# 03-POWER.net
KiCad netlist of a schematic drawn in Altium Designer
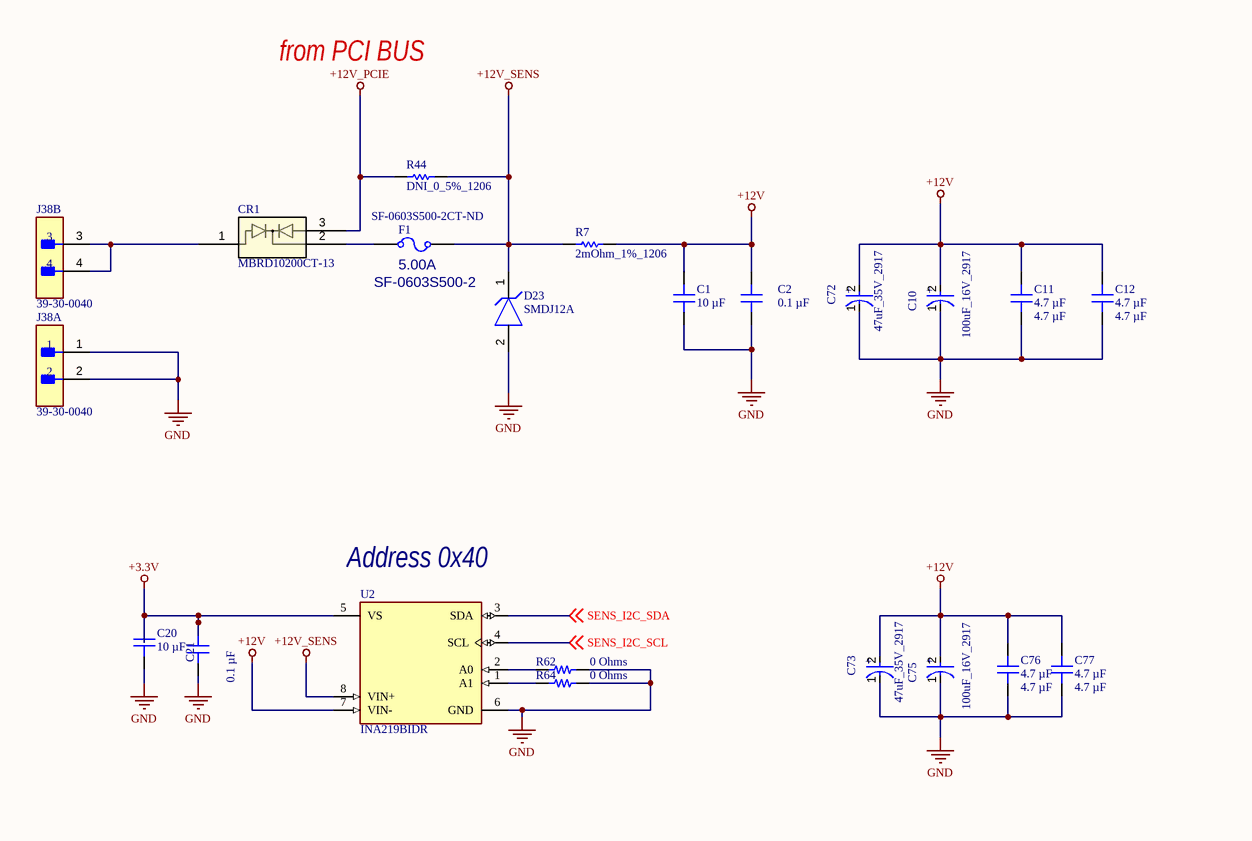
[diagram p0: 03-POWER.SchDoc, left]
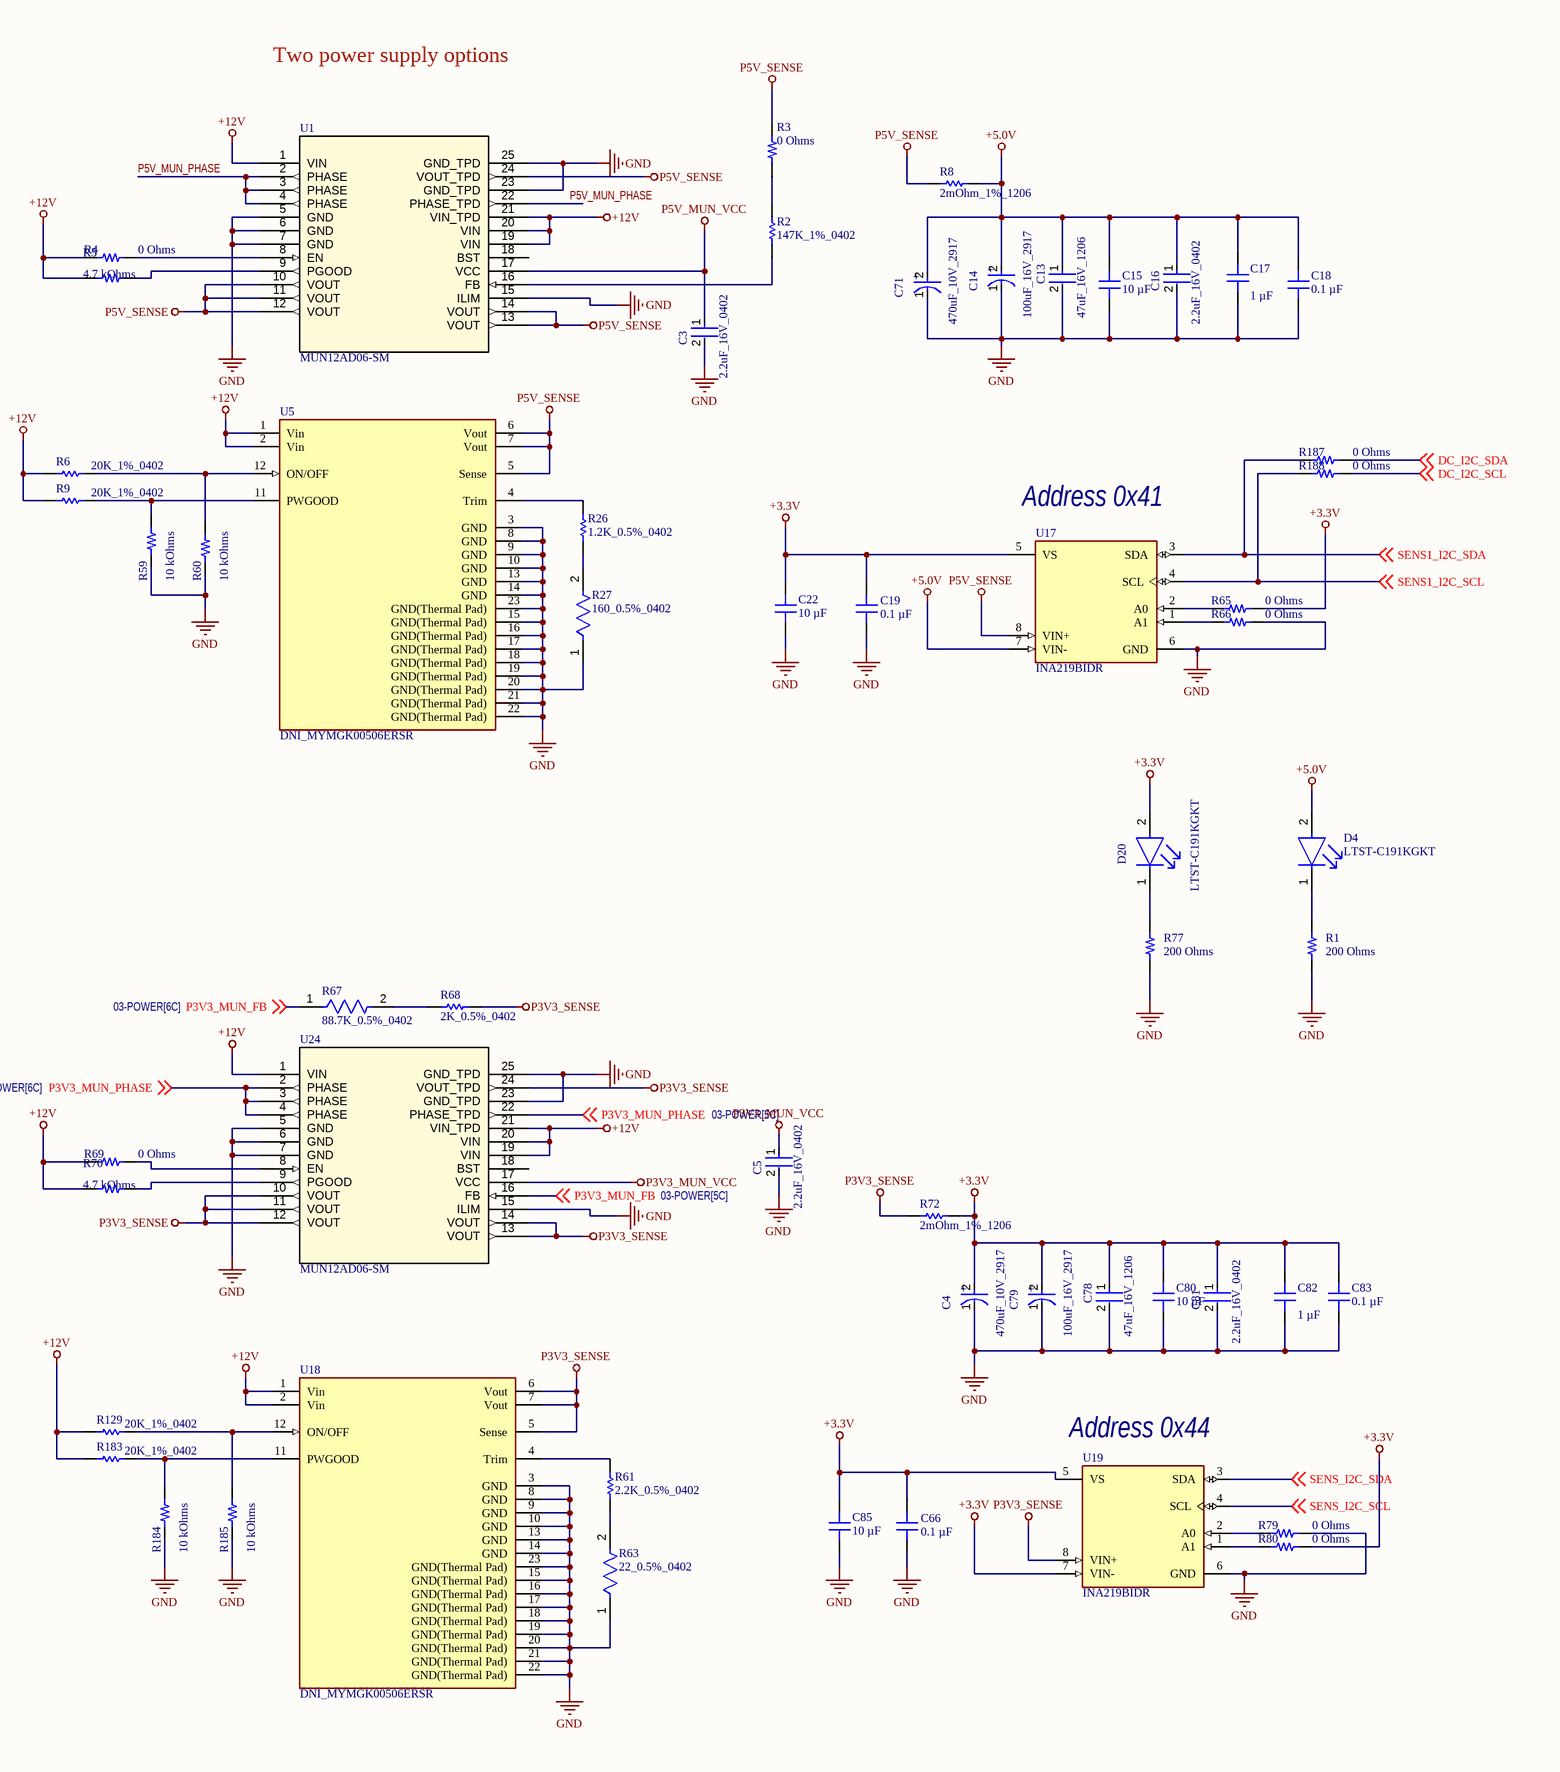
[diagram p1: 03-POWER.SchDoc, right]

(export (version "E")
  (design (tool "Eeschema 10.0.6"))
  (components
    (comp (ref "C1")
      (value "10 µF")
      (footprint "MURATA GRM21B 0805_2012")
      (description "CAP CER 10UF 25V X5R 0805")
      (fields
        (field (name "PART NUMBER") "GRM21BR61E106KA73L")
        (field (name "MANUFACTURER") "Murata Electronics")
      )
      (libsource (lib "Celestial Altium Library - altium_library") (part "Capacitor"))
    )
    (comp (ref "C2")
      (value "0.1 µF")
      (footprint "CAP 0402_1005")
      (description "CAP CER 0.1UF 50V X7R 0402")
      (fields (field (name "MANUFACTURER") "Yageo") (field (name "PART NUMBER") "CC0402KRX7R9BB104"))
      (libsource (lib "Celestial Altium Library - altium_library") (part "Capacitor"))
    )
    (comp (ref "C3")
      (value "2.2uF_16V_0402")
      (footprint "FP-C1005-050-0_05-IPC_A")
      (description "Multilayer Ceramic Capacitors 2.2μF ±10% 16V X5R SMD 0402")
      (fields (field (name "TOLERANCE") "10%"))
      (libsource (lib "Altium Content Vault") (part "b4654b650e69147ec39a6b967a45e02"))
    )
    (comp (ref "C4")
      (value "470uF_10V_2917")
      (footprint "FP-TAJE-MFG")
      (description "470uF 10V  ±10% 500mΩ 2917  SMD Tantalum Capacitor")
      (fields (field (name "TOLERANCE") "10%") (field (name "VOLTAGE") "10V"))
      (libsource (lib "Altium Content Vault") (part "203bc49f2ac43e59fd269a8c329ed05"))
    )
    (comp (ref "C5")
      (value "2.2uF_16V_0402")
      (footprint "FP-C1005-050-0_05-IPC_A")
      (description "Multilayer Ceramic Capacitors 2.2μF ±10% 16V X5R SMD 0402")
      (fields (field (name "TOLERANCE") "10%"))
      (libsource (lib "Altium Content Vault") (part "b4654b650e69147ec39a6b967a45e02"))
    )
    (comp (ref "C10")
      (value "100uF_16V_2917")
      (footprint "FP-T495D107K016ATE125-MFG")
      (description "CAP TANT 100UF 10% 16V 2917")
      (fields (field (name "VOLTAGE") "16V") (field (name "TOLERANCE") "10%"))
      (libsource (lib "Altium Content Vault") (part "a00bbbee19879c290e62620ae7e47b1"))
    )
    (comp (ref "C11")
      (value "4.7 µF")
      (footprint "MURATA CAP GRM31C 1206_3216")
      (description "CAP CER 4.7UF 50V X7R 1206")
      (fields
        (field (name "TOLERANCE") "±10%")
        (field (name "PART NUMBER") "GRM31CR71H475KA12L")
        (field (name "ALTIUM_VALUE") "4.7 µF")
      )
      (libsource (lib "Celestial Altium Library - altium_library") (part "Capacitor"))
    )
    (comp (ref "C12")
      (value "4.7 µF")
      (footprint "MURATA CAP GRM31C 1206_3216")
      (description "CAP CER 4.7UF 50V X7R 1206")
      (fields
        (field (name "TOLERANCE") "±10%")
        (field (name "PART NUMBER") "GRM31CR71H475KA12L")
        (field (name "ALTIUM_VALUE") "4.7 µF")
      )
      (libsource (lib "Celestial Altium Library - altium_library") (part "Capacitor"))
    )
    (comp (ref "C13")
      (value "47uF_16V_1206")
      (footprint "FP-C3216-160-0_2-MFG")
      (description "Multilayer Ceramic Capacitors 47uF ±20% 16V X5R SMD 1206")
      (fields (field (name "TOLERANCE") "20%"))
      (libsource (lib "Altium Content Vault") (part "11868f565c42a9108669ba33697ecf6"))
    )
    (comp (ref "C14")
      (value "100uF_16V_2917")
      (footprint "FP-T495D107K016ATE125-MFG")
      (description "CAP TANT 100UF 10% 16V 2917")
      (fields (field (name "VOLTAGE") "16V") (field (name "TOLERANCE") "10%"))
      (libsource (lib "Altium Content Vault") (part "a00bbbee19879c290e62620ae7e47b1"))
    )
    (comp (ref "C15")
      (value "10 µF")
      (footprint "MURATA GRM21B 0805_2012")
      (description "CAP CER 10UF 25V X5R 0805")
      (fields (field (name "TOLERANCE") "±10%") (field (name "PART NUMBER") "GRM21BR61E106KA73L"))
      (libsource (lib "Celestial Altium Library - altium_library") (part "Capacitor"))
    )
    (comp (ref "C16")
      (value "2.2uF_16V_0402")
      (footprint "FP-C1005-050-0_05-IPC_A")
      (description "Multilayer Ceramic Capacitors 2.2μF ±10% 16V X5R SMD 0402")
      (fields (field (name "TOLERANCE") "10%"))
      (libsource (lib "Altium Content Vault") (part "b4654b650e69147ec39a6b967a45e02"))
    )
    (comp (ref "C17")
      (value "1 µF")
      (footprint "CAP 0402_1005")
      (description "CAP CER 1UF 25V X5R 0402")
      (fields (field (name "TOLERANCE") "±10%") (field (name "PART NUMBER") "CC0402KRX5R8BB105"))
      (libsource (lib "Celestial Altium Library - altium_library") (part "Capacitor"))
    )
    (comp (ref "C18")
      (value "0.1 µF")
      (footprint "CAP 0402_1005")
      (description "CAP CER 0.1UF 50V X7R 0402")
      (fields (field (name "TOLERANCE") "±10%") (field (name "PART NUMBER") "CC0402KRX7R9BB104"))
      (libsource (lib "Celestial Altium Library - altium_library") (part "Capacitor"))
    )
    (comp (ref "C19")
      (value "0.1 µF")
      (footprint "CAP 0402_1005")
      (description "CAP CER 0.1UF 50V X7R 0402")
      (fields (field (name "PART NUMBER") "CC0402KRX7R9BB104") (field (name "MANUFACTURER") "Yageo"))
      (libsource (lib "Celestial Altium Library - altium_library") (part "Capacitor"))
    )
    (comp (ref "C20")
      (value "10 µF")
      (footprint "MURATA GRM21B 0805_2012")
      (description "CAP CER 10UF 25V X5R 0805")
      (fields (field (name "TOLERANCE") "±10%") (field (name "PART NUMBER") "GRM21BR61E106KA73L"))
      (libsource (lib "Celestial Altium Library - altium_library") (part "Capacitor"))
    )
    (comp (ref "C21")
      (value "0.1 µF")
      (footprint "CAP 0402_1005")
      (description "CAP CER 0.1UF 50V X7R 0402")
      (fields (field (name "PART NUMBER") "CC0402KRX7R9BB104") (field (name "MANUFACTURER") "Yageo"))
      (libsource (lib "Celestial Altium Library - altium_library") (part "Capacitor"))
    )
    (comp (ref "C22")
      (value "10 µF")
      (footprint "MURATA GRM21B 0805_2012")
      (description "CAP CER 10UF 25V X5R 0805")
      (fields (field (name "TOLERANCE") "±10%") (field (name "PART NUMBER") "GRM21BR61E106KA73L"))
      (libsource (lib "Celestial Altium Library - altium_library") (part "Capacitor"))
    )
    (comp (ref "C66")
      (value "0.1 µF")
      (footprint "CAP 0402_1005")
      (description "CAP CER 0.1UF 50V X7R 0402")
      (fields (field (name "PART NUMBER") "CC0402KRX7R9BB104") (field (name "MANUFACTURER") "Yageo"))
      (libsource (lib "Celestial Altium Library - altium_library") (part "Capacitor"))
    )
    (comp (ref "C71")
      (value "470uF_10V_2917")
      (footprint "FP-TAJE-MFG")
      (description "470uF 10V  ±10% 500mΩ 2917  SMD Tantalum Capacitor")
      (fields (field (name "TOLERANCE") "10%") (field (name "VOLTAGE") "10V"))
      (libsource (lib "Altium Content Vault") (part "203bc49f2ac43e59fd269a8c329ed05"))
    )
    (comp (ref "C72")
      (value "47uF_35V_2917")
      (footprint "FP-T521X476M035ATE030-MFG")
      (description "CAP TANT POLY 47UF 35V 2917")
      (fields (field (name "TOLERANCE") "20%"))
      (libsource (lib "Altium Content Vault") (part "a00bbbee19879c290e62620ae7e47b1"))
    )
    (comp (ref "C73")
      (value "47uF_35V_2917")
      (footprint "FP-T521X476M035ATE030-MFG")
      (description "CAP TANT POLY 47UF 35V 2917")
      (fields (field (name "TOLERANCE") "20%"))
      (libsource (lib "Altium Content Vault") (part "a00bbbee19879c290e62620ae7e47b1"))
    )
    (comp (ref "C75")
      (value "100uF_16V_2917")
      (footprint "FP-T495D107K016ATE125-MFG")
      (description "CAP TANT 100UF 10% 16V 2917")
      (fields (field (name "VOLTAGE") "16V") (field (name "TOLERANCE") "10%"))
      (libsource (lib "Altium Content Vault") (part "a00bbbee19879c290e62620ae7e47b1"))
    )
    (comp (ref "C76")
      (value "4.7 µF")
      (footprint "MURATA CAP GRM31C 1206_3216")
      (description "CAP CER 4.7UF 50V X7R 1206")
      (fields
        (field (name "TOLERANCE") "±10%")
        (field (name "PART NUMBER") "GRM31CR71H475KA12L")
        (field (name "ALTIUM_VALUE") "4.7 µF")
      )
      (libsource (lib "Celestial Altium Library - altium_library") (part "Capacitor"))
    )
    (comp (ref "C77")
      (value "4.7 µF")
      (footprint "MURATA CAP GRM31C 1206_3216")
      (description "CAP CER 4.7UF 50V X7R 1206")
      (fields
        (field (name "TOLERANCE") "±10%")
        (field (name "PART NUMBER") "GRM31CR71H475KA12L")
        (field (name "ALTIUM_VALUE") "4.7 µF")
      )
      (libsource (lib "Celestial Altium Library - altium_library") (part "Capacitor"))
    )
    (comp (ref "C78")
      (value "47uF_16V_1206")
      (footprint "FP-C3216-160-0_2-MFG")
      (description "Multilayer Ceramic Capacitors 47uF ±20% 16V X5R SMD 1206")
      (fields (field (name "TOLERANCE") "20%"))
      (libsource (lib "Altium Content Vault") (part "11868f565c42a9108669ba33697ecf6"))
    )
    (comp (ref "C79")
      (value "100uF_16V_2917")
      (footprint "FP-T495D107K016ATE125-MFG")
      (description "CAP TANT 100UF 10% 16V 2917")
      (fields (field (name "VOLTAGE") "16V") (field (name "TOLERANCE") "10%"))
      (libsource (lib "Altium Content Vault") (part "a00bbbee19879c290e62620ae7e47b1"))
    )
    (comp (ref "C80")
      (value "10 µF")
      (footprint "MURATA GRM21B 0805_2012")
      (description "CAP CER 10UF 25V X5R 0805")
      (fields (field (name "TOLERANCE") "±10%") (field (name "PART NUMBER") "GRM21BR61E106KA73L"))
      (libsource (lib "Celestial Altium Library - altium_library") (part "Capacitor"))
    )
    (comp (ref "C81")
      (value "2.2uF_16V_0402")
      (footprint "FP-C1005-050-0_05-IPC_A")
      (description "Multilayer Ceramic Capacitors 2.2μF ±10% 16V X5R SMD 0402")
      (fields (field (name "TOLERANCE") "10%"))
      (libsource (lib "Altium Content Vault") (part "b4654b650e69147ec39a6b967a45e02"))
    )
    (comp (ref "C82")
      (value "1 µF")
      (footprint "CAP 0402_1005")
      (description "CAP CER 1UF 25V X5R 0402")
      (fields (field (name "TOLERANCE") "±10%") (field (name "PART NUMBER") "CC0402KRX5R8BB105"))
      (libsource (lib "Celestial Altium Library - altium_library") (part "Capacitor"))
    )
    (comp (ref "C83")
      (value "0.1 µF")
      (footprint "CAP 0402_1005")
      (description "CAP CER 0.1UF 50V X7R 0402")
      (fields (field (name "TOLERANCE") "±10%") (field (name "PART NUMBER") "CC0402KRX7R9BB104"))
      (libsource (lib "Celestial Altium Library - altium_library") (part "Capacitor"))
    )
    (comp (ref "C85")
      (value "10 µF")
      (footprint "MURATA GRM21B 0805_2012")
      (description "CAP CER 10UF 25V X5R 0805")
      (fields (field (name "TOLERANCE") "±10%") (field (name "PART NUMBER") "GRM21BR61E106KA73L"))
      (libsource (lib "Celestial Altium Library - altium_library") (part "Capacitor"))
    )
    (comp (ref "CR1")
      (value "MBRD10200CT-13")
      (footprint "TO252(DPAK)_DIO")
      (description "No Description Available")
      (libsource (lib "MBRD10200CT-13") (part "MBRD10200CT-13"))
    )
    (comp (ref "D4")
      (value "LTST-C191KGKT")
      (footprint "FP-LTST-C191KGKT-MFG")
      (description "LED GREEN CLEAR SMD")
      (libsource (lib "Altium Content Vault") (part "8706943c75ba83719d021d2fdc84c58"))
    )
    (comp (ref "D20")
      (value "LTST-C191KGKT")
      (footprint "FP-LTST-C191KGKT-MFG")
      (description "LED GREEN CLEAR SMD")
      (libsource (lib "Altium Content Vault") (part "8706943c75ba83719d021d2fdc84c58"))
    )
    (comp (ref "D23")
      (value "SMDJ12A")
      (footprint "FP-DO-214AB_SMC_J-Bend-MFG")
      (description "TVS DIODE 12V 19.9V DO214AB")
      (libsource (lib "Altium Content Vault") (part "673ecd2ea4d7fb87b4005b0cb348b7d"))
    )
    (comp (ref "F1")
      (value "5.00A")
      (footprint "FUSM1608X60N")
      (description "FUSE SLOW 5.00A 32V M 0603")
      (fields
        (field (name "MFG PART NUM") "SF-0603S500-2")
        (field (name "VALENTIUM PART NUM") "<VALENTIUM>")
        (field (name "SUPPLIER PART NUMBER 1") "SF-0603S500-2CT-ND")
        (field (name "Comment") "FUSE_0603_5.00A")
      )
      (libsource (lib "Passives") (part "FUSE_0603_2.00A"))
    )
    (comp (ref "J38")
      (value "39-30-0040")
      (footprint "FP-39-30-0040-MFG")
      (description "CONN HEADER R/A 4POS 4.2MM")
      (fields
        (field (name "OCTOPART") "https://octopart.com/39-30-0040-molex-277428")
        (field (name "MANUFACTURER") "Molex")
      )
      (libsource (lib "Altium Content Vault") (part "ac72c5313ea981db199dbd0e8237b04"))
    )
    (comp (ref "R1")
      (value "200 Ohms")
      (footprint "YAGEO RES 0402_1005")
      (description "RES 200 OHM 1% 1/16W 0402")
      (fields (field (name "TOLERANCE") "±1%") (field (name "PART NUMBER") "RC0402FR-07200RL"))
      (libsource (lib "Celestial Altium Library - altium_library") (part "Resistor"))
    )
    (comp (ref "R2")
      (value "147K_1%_0402")
      (footprint "RESC1005X40X25ML05T10")
      (fields (field (name "MANUFACTURER") "Yageo / Phycomp") (field (name "PART NUMBER") "RC0402FR-07147KL"))
      (libsource (lib "Altium Content Vault") (part "RES"))
    )
    (comp (ref "R3")
      (value "0 Ohms")
      (footprint "YAGEO RES 0402_1005")
      (description "RES 0 OHM JUMPER 1/16W 0402")
      (fields (field (name "MANUFACTURER") "Yageo") (field (name "TOLERANCE") "Jumper"))
      (libsource (lib "Celestial Altium Library - altium_library") (part "Resistor"))
    )
    (comp (ref "R4")
      (value "0 Ohms")
      (footprint "YAGEO RES 0402_1005")
      (description "RES 0 OHM JUMPER 1/16W 0402")
      (fields (field (name "MANUFACTURER") "Yageo") (field (name "TOLERANCE") "Jumper"))
      (libsource (lib "Celestial Altium Library - altium_library") (part "Resistor"))
    )
    (comp (ref "R5")
      (value "4.7 kOhms")
      (footprint "YAGEO RES 0402_1005")
      (description "RES 4.7K OHM 1% 1/16W 0402")
      (fields (field (name "MANUFACTURER") "Yageo") (field (name "PART NUMBER") "RC0402FR-074K7L"))
      (libsource (lib "Celestial Altium Library - altium_library") (part "Resistor"))
    )
    (comp (ref "R6")
      (value "20K_1%_0402")
      (footprint "RESC1005X40X25NL10T10")
      (fields (field (name "PART NUMBER") "MC00625W0402120K") (field (name "MANUFACTURER") "Multicomp"))
      (libsource (lib "Altium Content Vault") (part "RES"))
    )
    (comp (ref "R7")
      (value "2mOhm_1%_1206")
      (footprint "RESC3216X89X64NL25T25")
      (fields (field (name "MANUFACTURER") "Vishay Dale") (field (name "PART NUMBER") "WSL12062L000FEA18"))
      (libsource (lib "Altium Content Vault") (part "RES"))
    )
    (comp (ref "R8")
      (value "2mOhm_1%_1206")
      (footprint "RESC3216X89X64NL25T25")
      (fields (field (name "MANUFACTURER") "Vishay Dale") (field (name "PART NUMBER") "WSL12062L000FEA18"))
      (libsource (lib "Altium Content Vault") (part "RES"))
    )
    (comp (ref "R9")
      (value "20K_1%_0402")
      (footprint "RESC1005X40X25NL10T10")
      (fields (field (name "PART NUMBER") "MC00625W0402120K") (field (name "MANUFACTURER") "Multicomp"))
      (libsource (lib "Altium Content Vault") (part "RES"))
    )
    (comp (ref "R26")
      (value "1.2K_0.5%_0402")
      (footprint "RESC1005X40X25ML10T10")
      (fields (field (name "PART NUMBER") "ERA-2AED122X") (field (name "MANUFACTURER") "Panasonic"))
      (libsource (lib "Altium Content Vault") (part "RES"))
    )
    (comp (ref "R27")
      (value "160_0.5%_0402")
      (footprint "FP-RT0402-MFG")
      (description "RES SMD 160 OHM 0.5% 1/16W 0402")
      (fields
        (field (name "TOLERANCE") "0.005")
        (field (name "OCTOPART") "https://octopart.com/rt0402dre07160rl-yageo-1216058")
      )
      (libsource (lib "Altium Content Vault") (part "1029c3af85768c4190bb7ad29bc67b5"))
    )
    (comp (ref "R44")
      (value "DNI_0_5%_1206")
      (footprint "RESC3116X65X50ML20T20")
      (fields (field (name "PART NUMBER") "CRCW12060000Z0EAHP") (field (name "MANUFACTURER") "Vishay Dale"))
      (libsource (lib "Altium Content Vault") (part "RES"))
    )
    (comp (ref "R59")
      (value "10 kOhms")
      (footprint "YAGEO RES 0402_1005")
      (description "RES 10K OHM 1% 1/16W 0402")
      (fields (field (name "MANUFACTURER") "Yageo") (field (name "PART NUMBER") "RC0402FR-0710KL"))
      (libsource (lib "Celestial Altium Library - altium_library") (part "Resistor"))
    )
    (comp (ref "R60")
      (value "10 kOhms")
      (footprint "YAGEO RES 0402_1005")
      (description "RES 10K OHM 1% 1/16W 0402")
      (fields (field (name "MANUFACTURER") "Yageo") (field (name "PART NUMBER") "RC0402FR-0710KL"))
      (libsource (lib "Celestial Altium Library - altium_library") (part "Resistor"))
    )
    (comp (ref "R61")
      (value "2.2K_0.5%_0402")
      (footprint "RESC1005X40X25ML10T10")
      (fields (field (name "PART NUMBER") "ERA-2AED222X") (field (name "MANUFACTURER") "Panasonic"))
      (libsource (lib "Altium Content Vault") (part "RES"))
    )
    (comp (ref "R62")
      (value "0 Ohms")
      (footprint "YAGEO RES 0402_1005")
      (description "RES 0 OHM JUMPER 1/16W 0402")
      (fields (field (name "MANUFACTURER") "Yageo") (field (name "TOLERANCE") "Jumper"))
      (libsource (lib "Celestial Altium Library - altium_library") (part "Resistor"))
    )
    (comp (ref "R63")
      (value "22_0.5%_0402")
      (footprint "FP-RG1005-IPC_A")
      (description "Automotive Metal Thin Film Chip Resistor, 0402, 22Ω, 0.5%, 100ppm/°C, 0.0625W, 75V")
      (fields (field (name "TOLERANCE") "0.5%"))
      (libsource (lib "Altium Content Vault") (part "1029c3af85768c4190bb7ad29bc67b5"))
    )
    (comp (ref "R64")
      (value "0 Ohms")
      (footprint "YAGEO RES 0402_1005")
      (description "RES 0 OHM JUMPER 1/16W 0402")
      (fields (field (name "MANUFACTURER") "Yageo") (field (name "TOLERANCE") "Jumper"))
      (libsource (lib "Celestial Altium Library - altium_library") (part "Resistor"))
    )
    (comp (ref "R65")
      (value "0 Ohms")
      (footprint "YAGEO RES 0402_1005")
      (description "RES 0 OHM JUMPER 1/16W 0402")
      (fields (field (name "MANUFACTURER") "Yageo") (field (name "TOLERANCE") "Jumper"))
      (libsource (lib "Celestial Altium Library - altium_library") (part "Resistor"))
    )
    (comp (ref "R66")
      (value "0 Ohms")
      (footprint "YAGEO RES 0402_1005")
      (description "RES 0 OHM JUMPER 1/16W 0402")
      (fields (field (name "MANUFACTURER") "Yageo") (field (name "TOLERANCE") "Jumper"))
      (libsource (lib "Celestial Altium Library - altium_library") (part "Resistor"))
    )
    (comp (ref "R67")
      (value "88.7K_0.5%_0402")
      (footprint "FP-RT0402-MFG")
      (description "RES SMD 88.7K OHM 0.5% 1/16W")
      (fields
        (field (name "OCTOPART") "https://octopart.com/rt0402dre0788k7l-yageo-1439224")
        (field (name "MANUFACTURER") "Yageo")
      )
      (libsource (lib "Altium Content Vault") (part "1029c3af85768c4190bb7ad29bc67b5"))
    )
    (comp (ref "R68")
      (value "2K_0.5%_0402")
      (footprint "RESC1005X35X25LL10T10")
      (fields (field (name "PART NUMBER") "RT0402DRD072KL") (field (name "MANUFACTURER") "Yageo"))
      (libsource (lib "Altium Content Vault") (part "RES"))
    )
    (comp (ref "R69")
      (value "0 Ohms")
      (footprint "YAGEO RES 0402_1005")
      (description "RES 0 OHM JUMPER 1/16W 0402")
      (fields (field (name "MANUFACTURER") "Yageo") (field (name "TOLERANCE") "Jumper"))
      (libsource (lib "Celestial Altium Library - altium_library") (part "Resistor"))
    )
    (comp (ref "R70")
      (value "4.7 kOhms")
      (footprint "YAGEO RES 0402_1005")
      (description "RES 4.7K OHM 1% 1/16W 0402")
      (fields (field (name "MANUFACTURER") "Yageo") (field (name "PART NUMBER") "RC0402FR-074K7L"))
      (libsource (lib "Celestial Altium Library - altium_library") (part "Resistor"))
    )
    (comp (ref "R72")
      (value "2mOhm_1%_1206")
      (footprint "RESC3216X89X64NL25T25")
      (fields (field (name "MANUFACTURER") "Vishay Dale") (field (name "PART NUMBER") "WSL12062L000FEA18"))
      (libsource (lib "Altium Content Vault") (part "RES"))
    )
    (comp (ref "R77")
      (value "200 Ohms")
      (footprint "YAGEO RES 0402_1005")
      (description "RES 200 OHM 1% 1/16W 0402")
      (fields (field (name "TOLERANCE") "±1%") (field (name "PART NUMBER") "RC0402FR-07200RL"))
      (libsource (lib "Celestial Altium Library - altium_library") (part "Resistor"))
    )
    (comp (ref "R79")
      (value "0 Ohms")
      (footprint "YAGEO RES 0402_1005")
      (description "RES 0 OHM JUMPER 1/16W 0402")
      (fields (field (name "MANUFACTURER") "Yageo") (field (name "TOLERANCE") "Jumper"))
      (libsource (lib "Celestial Altium Library - altium_library") (part "Resistor"))
    )
    (comp (ref "R80")
      (value "0 Ohms")
      (footprint "YAGEO RES 0402_1005")
      (description "RES 0 OHM JUMPER 1/16W 0402")
      (fields (field (name "MANUFACTURER") "Yageo") (field (name "TOLERANCE") "Jumper"))
      (libsource (lib "Celestial Altium Library - altium_library") (part "Resistor"))
    )
    (comp (ref "R129")
      (value "20K_1%_0402")
      (footprint "RESC1005X40X25NL10T10")
      (fields (field (name "PART NUMBER") "MC00625W0402120K") (field (name "MANUFACTURER") "Multicomp"))
      (libsource (lib "Altium Content Vault") (part "RES"))
    )
    (comp (ref "R183")
      (value "20K_1%_0402")
      (footprint "RESC1005X40X25NL10T10")
      (fields (field (name "PART NUMBER") "MC00625W0402120K") (field (name "MANUFACTURER") "Multicomp"))
      (libsource (lib "Altium Content Vault") (part "RES"))
    )
    (comp (ref "R184")
      (value "10 kOhms")
      (footprint "YAGEO RES 0402_1005")
      (description "RES 10K OHM 1% 1/16W 0402")
      (fields (field (name "MANUFACTURER") "Yageo") (field (name "PART NUMBER") "RC0402FR-0710KL"))
      (libsource (lib "Celestial Altium Library - altium_library") (part "Resistor"))
    )
    (comp (ref "R185")
      (value "10 kOhms")
      (footprint "YAGEO RES 0402_1005")
      (description "RES 10K OHM 1% 1/16W 0402")
      (fields (field (name "MANUFACTURER") "Yageo") (field (name "PART NUMBER") "RC0402FR-0710KL"))
      (libsource (lib "Celestial Altium Library - altium_library") (part "Resistor"))
    )
    (comp (ref "R187")
      (value "0 Ohms")
      (footprint "YAGEO RES 0402_1005")
      (description "RES 0 OHM JUMPER 1/16W 0402")
      (fields (field (name "MANUFACTURER") "Yageo") (field (name "TOLERANCE") "Jumper"))
      (libsource (lib "Celestial Altium Library - altium_library") (part "Resistor"))
    )
    (comp (ref "R188")
      (value "0 Ohms")
      (footprint "YAGEO RES 0402_1005")
      (description "RES 0 OHM JUMPER 1/16W 0402")
      (fields (field (name "MANUFACTURER") "Yageo") (field (name "TOLERANCE") "Jumper"))
      (libsource (lib "Celestial Altium Library - altium_library") (part "Resistor"))
    )
    (comp (ref "U1")
      (value "MUN12AD06-SM")
      (footprint "MUN12AD06-SM_CYN")
      (description "No Description Available")
      (libsource (lib "MUN12AD06-SM") (part "MUN12AD06-SM"))
    )
    (comp (ref "U2")
      (value "INA219BIDR")
      (footprint "FP-D0008A-MFG")
      (description "IC MONITOR PWR/CURR BIDIR 8-SOIC")
      (libsource (lib "Altium Content Vault") (part "41cc1aee4cbc9fa2660a15773fa0e79"))
    )
    (comp (ref "U5")
      (value "DNI_MYMGK00506ERSR")
      (footprint "FP-MYMGK-12-MFG")
      (description "DC DC CONVERTER 0.7-5V")
      (libsource (lib "Altium Content Vault") (part "57b8017c1ce60d7b1362a625e7a4ba1"))
    )
    (comp (ref "U17")
      (value "INA219BIDR")
      (footprint "FP-D0008A-MFG")
      (description "IC MONITOR PWR/CURR BIDIR 8-SOIC")
      (libsource (lib "Altium Content Vault") (part "41cc1aee4cbc9fa2660a15773fa0e79"))
    )
    (comp (ref "U18")
      (value "DNI_MYMGK00506ERSR")
      (footprint "FP-MYMGK-12-MFG")
      (description "DC DC CONVERTER 0.7-5V")
      (libsource (lib "Altium Content Vault") (part "57b8017c1ce60d7b1362a625e7a4ba1"))
    )
    (comp (ref "U19")
      (value "INA219BIDR")
      (footprint "FP-D0008A-MFG")
      (description "IC MONITOR PWR/CURR BIDIR 8-SOIC")
      (libsource (lib "Altium Content Vault") (part "41cc1aee4cbc9fa2660a15773fa0e79"))
    )
    (comp (ref "U24")
      (value "MUN12AD06-SM")
      (footprint "MUN12AD06-SM_CYN")
      (description "No Description Available")
      (libsource (lib "MUN12AD06-SM") (part "MUN12AD06-SM"))
    )
  )
  (nets
    (net (code "1") (name "+3.3V") (class "Default")
      (node (ref "C19") (pin "2") (pinfunction "2_2") (pintype "passive"))
      (node (ref "C20") (pin "2") (pinfunction "2_2") (pintype "passive"))
      (node (ref "C21") (pin "2") (pinfunction "2_2") (pintype "passive"))
      (node (ref "C22") (pin "2") (pinfunction "2_2") (pintype "passive"))
      (node (ref "C4") (pin "2") (pinfunction "A_2") (pintype "passive"))
      (node (ref "C66") (pin "2") (pinfunction "2_2") (pintype "passive"))
      (node (ref "C78") (pin "1") (pinfunction "1_1") (pintype "passive"))
      (node (ref "C79") (pin "2") (pinfunction "A_2") (pintype "passive"))
      (node (ref "C80") (pin "2") (pinfunction "2_2") (pintype "passive"))
      (node (ref "C81") (pin "1") (pinfunction "1_1") (pintype "passive"))
      (node (ref "C82") (pin "2") (pinfunction "2_2") (pintype "passive"))
      (node (ref "C83") (pin "1") (pinfunction "1_1") (pintype "passive"))
      (node (ref "C85") (pin "2") (pinfunction "2_2") (pintype "passive"))
      (node (ref "D20") (pin "2") (pinfunction "A_2") (pintype "passive"))
      (node (ref "R65") (pin "2") (pinfunction "2_2") (pintype "passive"))
      (node (ref "R72") (pin "2") (pinfunction "2_2") (pintype "passive"))
      (node (ref "R80") (pin "2") (pinfunction "2_2") (pintype "passive"))
      (node (ref "U17") (pin "5") (pinfunction "VS_5") (pintype "power_in"))
      (node (ref "U19") (pin "5") (pinfunction "VS_5") (pintype "power_in"))
      (node (ref "U19") (pin "7") (pinfunction "VIN-_7") (pintype "input"))
      (node (ref "U2") (pin "5") (pinfunction "VS_5") (pintype "power_in"))
    )
    (net (code "2") (name "+5.0V") (class "Default")
      (node (ref "C13") (pin "1") (pinfunction "1_1") (pintype "passive"))
      (node (ref "C14") (pin "2") (pinfunction "A_2") (pintype "passive"))
      (node (ref "C15") (pin "2") (pinfunction "2_2") (pintype "passive"))
      (node (ref "C16") (pin "1") (pinfunction "1_1") (pintype "passive"))
      (node (ref "C17") (pin "2") (pinfunction "2_2") (pintype "passive"))
      (node (ref "C18") (pin "1") (pinfunction "1_1") (pintype "passive"))
      (node (ref "C71") (pin "2") (pinfunction "A_2") (pintype "passive"))
      (node (ref "D4") (pin "2") (pinfunction "A_2") (pintype "passive"))
      (node (ref "R8") (pin "2") (pinfunction "2_2") (pintype "passive"))
      (node (ref "U17") (pin "7") (pinfunction "VIN-_7") (pintype "input"))
    )
    (net (code "3") (name "+12V") (class "Default")
      (node (ref "C1") (pin "1") (pinfunction "1_1") (pintype "passive"))
      (node (ref "C10") (pin "2") (pinfunction "A_2") (pintype "passive"))
      (node (ref "C11") (pin "2") (pinfunction "2_2") (pintype "passive"))
      (node (ref "C12") (pin "2") (pinfunction "2_2") (pintype "passive"))
      (node (ref "C2") (pin "2") (pinfunction "2_2") (pintype "passive"))
      (node (ref "C72") (pin "2") (pinfunction "A_2") (pintype "passive"))
      (node (ref "C73") (pin "2") (pinfunction "A_2") (pintype "passive"))
      (node (ref "C75") (pin "2") (pinfunction "A_2") (pintype "passive"))
      (node (ref "C76") (pin "2") (pinfunction "2_2") (pintype "passive"))
      (node (ref "C77") (pin "2") (pinfunction "2_2") (pintype "passive"))
      (node (ref "R129") (pin "1") (pinfunction "1_1") (pintype "passive"))
      (node (ref "R183") (pin "1") (pinfunction "1_1") (pintype "passive"))
      (node (ref "R4") (pin "1") (pinfunction "1_1") (pintype "passive"))
      (node (ref "R5") (pin "2") (pinfunction "2_2") (pintype "passive"))
      (node (ref "R6") (pin "1") (pinfunction "1_1") (pintype "passive"))
      (node (ref "R69") (pin "1") (pinfunction "1_1") (pintype "passive"))
      (node (ref "R7") (pin "2") (pinfunction "2_2") (pintype "passive"))
      (node (ref "R70") (pin "2") (pinfunction "2_2") (pintype "passive"))
      (node (ref "R9") (pin "1") (pinfunction "1_1") (pintype "passive"))
      (node (ref "U1") (pin "1") (pinfunction "VIN_1") (pintype "power_in"))
      (node (ref "U1") (pin "19") (pinfunction "VIN_19") (pintype "power_in"))
      (node (ref "U1") (pin "20") (pinfunction "VIN_20") (pintype "power_in"))
      (node (ref "U1") (pin "21") (pinfunction "VIN_TPD_21") (pintype "power_in"))
      (node (ref "U18") (pin "1") (pinfunction "Vin_1") (pintype "power_in"))
      (node (ref "U18") (pin "2") (pinfunction "Vin_2") (pintype "power_in"))
      (node (ref "U2") (pin "7") (pinfunction "VIN-_7") (pintype "input"))
      (node (ref "U24") (pin "1") (pinfunction "VIN_1") (pintype "power_in"))
      (node (ref "U24") (pin "19") (pinfunction "VIN_19") (pintype "power_in"))
      (node (ref "U24") (pin "20") (pinfunction "VIN_20") (pintype "power_in"))
      (node (ref "U24") (pin "21") (pinfunction "VIN_TPD_21") (pintype "power_in"))
      (node (ref "U5") (pin "1") (pinfunction "Vin_1") (pintype "power_in"))
      (node (ref "U5") (pin "2") (pinfunction "Vin_2") (pintype "power_in"))
    )
    (net (code "4") (name "+12V_PCIE") (class "Default")
      (node (ref "CR1") (pin "3") (pinfunction "3_3") (pintype "passive"))
      (node (ref "R44") (pin "1") (pinfunction "1_1") (pintype "passive"))
    )
    (net (code "5") (name "+12V_SENS") (class "Default")
      (node (ref "D23") (pin "1") (pinfunction "C_1") (pintype "passive"))
      (node (ref "F1") (pin "2") (pinfunction "2_2") (pintype "passive"))
      (node (ref "R44") (pin "2") (pinfunction "2_2") (pintype "passive"))
      (node (ref "R7") (pin "1") (pinfunction "1_1") (pintype "passive"))
      (node (ref "U2") (pin "8") (pinfunction "VIN+_8") (pintype "input"))
    )
    (net (code "6") (name "/P5V_MUN_PHASE") (class "Default")
      (node (ref "U1") (pin "2") (pinfunction "PHASE_2") (pintype "output"))
      (node (ref "U1") (pin "22") (pinfunction "PHASE_TPD_22") (pintype "output"))
      (node (ref "U1") (pin "3") (pinfunction "PHASE_3") (pintype "output"))
      (node (ref "U1") (pin "4") (pinfunction "PHASE_4") (pintype "output"))
    )
    (net (code "7") (name "DC_I2C_SCL") (class "Default")
      (node (ref "R188") (pin "2") (pinfunction "2_2") (pintype "passive"))
    )
    (net (code "8") (name "DC_I2C_SDA") (class "Default")
      (node (ref "R187") (pin "2") (pinfunction "2_2") (pintype "passive"))
    )
    (net (code "9") (name "GND") (class "Default")
      (node (ref "C1") (pin "2") (pinfunction "2_2") (pintype "passive"))
      (node (ref "C10") (pin "1") (pinfunction "C_1") (pintype "passive"))
      (node (ref "C11") (pin "1") (pinfunction "1_1") (pintype "passive"))
      (node (ref "C12") (pin "1") (pinfunction "1_1") (pintype "passive"))
      (node (ref "C13") (pin "2") (pinfunction "2_2") (pintype "passive"))
      (node (ref "C14") (pin "1") (pinfunction "C_1") (pintype "passive"))
      (node (ref "C15") (pin "1") (pinfunction "1_1") (pintype "passive"))
      (node (ref "C16") (pin "2") (pinfunction "2_2") (pintype "passive"))
      (node (ref "C17") (pin "1") (pinfunction "1_1") (pintype "passive"))
      (node (ref "C18") (pin "2") (pinfunction "2_2") (pintype "passive"))
      (node (ref "C19") (pin "1") (pinfunction "1_1") (pintype "passive"))
      (node (ref "C2") (pin "1") (pinfunction "1_1") (pintype "passive"))
      (node (ref "C20") (pin "1") (pinfunction "1_1") (pintype "passive"))
      (node (ref "C21") (pin "1") (pinfunction "1_1") (pintype "passive"))
      (node (ref "C22") (pin "1") (pinfunction "1_1") (pintype "passive"))
      (node (ref "C3") (pin "2") (pinfunction "2_2") (pintype "passive"))
      (node (ref "C4") (pin "1") (pinfunction "C_1") (pintype "passive"))
      (node (ref "C5") (pin "2") (pinfunction "2_2") (pintype "passive"))
      (node (ref "C66") (pin "1") (pinfunction "1_1") (pintype "passive"))
      (node (ref "C71") (pin "1") (pinfunction "C_1") (pintype "passive"))
      (node (ref "C72") (pin "1") (pinfunction "C_1") (pintype "passive"))
      (node (ref "C73") (pin "1") (pinfunction "C_1") (pintype "passive"))
      (node (ref "C75") (pin "1") (pinfunction "C_1") (pintype "passive"))
      (node (ref "C76") (pin "1") (pinfunction "1_1") (pintype "passive"))
      (node (ref "C77") (pin "1") (pinfunction "1_1") (pintype "passive"))
      (node (ref "C78") (pin "2") (pinfunction "2_2") (pintype "passive"))
      (node (ref "C79") (pin "1") (pinfunction "C_1") (pintype "passive"))
      (node (ref "C80") (pin "1") (pinfunction "1_1") (pintype "passive"))
      (node (ref "C81") (pin "2") (pinfunction "2_2") (pintype "passive"))
      (node (ref "C82") (pin "1") (pinfunction "1_1") (pintype "passive"))
      (node (ref "C83") (pin "2") (pinfunction "2_2") (pintype "passive"))
      (node (ref "C85") (pin "1") (pinfunction "1_1") (pintype "passive"))
      (node (ref "D23") (pin "2") (pinfunction "A_2") (pintype "passive"))
      (node (ref "J38") (pin "1") (pinfunction "1_1") (pintype "passive"))
      (node (ref "J38") (pin "2") (pinfunction "2_2") (pintype "passive"))
      (node (ref "R1") (pin "1") (pinfunction "1_1") (pintype "passive"))
      (node (ref "R184") (pin "1") (pinfunction "1_1") (pintype "passive"))
      (node (ref "R185") (pin "1") (pinfunction "1_1") (pintype "passive"))
      (node (ref "R27") (pin "1") (pinfunction "1_1") (pintype "passive"))
      (node (ref "R59") (pin "1") (pinfunction "1_1") (pintype "passive"))
      (node (ref "R60") (pin "1") (pinfunction "1_1") (pintype "passive"))
      (node (ref "R62") (pin "2") (pinfunction "2_2") (pintype "passive"))
      (node (ref "R63") (pin "1") (pinfunction "1_1") (pintype "passive"))
      (node (ref "R64") (pin "2") (pinfunction "2_2") (pintype "passive"))
      (node (ref "R66") (pin "2") (pinfunction "2_2") (pintype "passive"))
      (node (ref "R77") (pin "1") (pinfunction "1_1") (pintype "passive"))
      (node (ref "R79") (pin "2") (pinfunction "2_2") (pintype "passive"))
      (node (ref "U1") (pin "15") (pinfunction "ILIM_15") (pintype "passive"))
      (node (ref "U1") (pin "23") (pinfunction "GND_TPD_23") (pintype "power_in"))
      (node (ref "U1") (pin "25") (pinfunction "GND_TPD_25") (pintype "power_in"))
      (node (ref "U1") (pin "5") (pinfunction "GND_5") (pintype "power_in"))
      (node (ref "U1") (pin "6") (pinfunction "GND_6") (pintype "power_in"))
      (node (ref "U1") (pin "7") (pinfunction "GND_7") (pintype "power_in"))
      (node (ref "U17") (pin "6") (pinfunction "GND_6") (pintype "power_in"))
      (node (ref "U18") (pin "10") (pinfunction "GND_10") (pintype "power_in"))
      (node (ref "U18") (pin "13") (pinfunction "GND_13") (pintype "power_in"))
      (node (ref "U18") (pin "14") (pinfunction "GND_14") (pintype "power_in"))
      (node (ref "U18") (pin "15") (pinfunction "GND(Thermal_Pad)_15") (pintype "power_in"))
      (node (ref "U18") (pin "16") (pinfunction "GND(Thermal_Pad)_16") (pintype "power_in"))
      (node (ref "U18") (pin "17") (pinfunction "GND(Thermal_Pad)_17") (pintype "power_in"))
      (node (ref "U18") (pin "18") (pinfunction "GND(Thermal_Pad)_18") (pintype "power_in"))
      (node (ref "U18") (pin "19") (pinfunction "GND(Thermal_Pad)_19") (pintype "power_in"))
      (node (ref "U18") (pin "20") (pinfunction "GND(Thermal_Pad)_20") (pintype "power_in"))
      (node (ref "U18") (pin "21") (pinfunction "GND(Thermal_Pad)_21") (pintype "power_in"))
      (node (ref "U18") (pin "22") (pinfunction "GND(Thermal_Pad)_22") (pintype "power_in"))
      (node (ref "U18") (pin "23") (pinfunction "GND(Thermal_Pad)_23") (pintype "power_in"))
      (node (ref "U18") (pin "3") (pinfunction "GND_3") (pintype "power_in"))
      (node (ref "U18") (pin "8") (pinfunction "GND_8") (pintype "power_in"))
      (node (ref "U18") (pin "9") (pinfunction "GND_9") (pintype "power_in"))
      (node (ref "U19") (pin "6") (pinfunction "GND_6") (pintype "power_in"))
      (node (ref "U2") (pin "6") (pinfunction "GND_6") (pintype "power_in"))
      (node (ref "U24") (pin "15") (pinfunction "ILIM_15") (pintype "passive"))
      (node (ref "U24") (pin "23") (pinfunction "GND_TPD_23") (pintype "power_in"))
      (node (ref "U24") (pin "25") (pinfunction "GND_TPD_25") (pintype "power_in"))
      (node (ref "U24") (pin "5") (pinfunction "GND_5") (pintype "power_in"))
      (node (ref "U24") (pin "6") (pinfunction "GND_6") (pintype "power_in"))
      (node (ref "U24") (pin "7") (pinfunction "GND_7") (pintype "power_in"))
      (node (ref "U5") (pin "10") (pinfunction "GND_10") (pintype "power_in"))
      (node (ref "U5") (pin "13") (pinfunction "GND_13") (pintype "power_in"))
      (node (ref "U5") (pin "14") (pinfunction "GND_14") (pintype "power_in"))
      (node (ref "U5") (pin "15") (pinfunction "GND(Thermal_Pad)_15") (pintype "power_in"))
      (node (ref "U5") (pin "16") (pinfunction "GND(Thermal_Pad)_16") (pintype "power_in"))
      (node (ref "U5") (pin "17") (pinfunction "GND(Thermal_Pad)_17") (pintype "power_in"))
      (node (ref "U5") (pin "18") (pinfunction "GND(Thermal_Pad)_18") (pintype "power_in"))
      (node (ref "U5") (pin "19") (pinfunction "GND(Thermal_Pad)_19") (pintype "power_in"))
      (node (ref "U5") (pin "20") (pinfunction "GND(Thermal_Pad)_20") (pintype "power_in"))
      (node (ref "U5") (pin "21") (pinfunction "GND(Thermal_Pad)_21") (pintype "power_in"))
      (node (ref "U5") (pin "22") (pinfunction "GND(Thermal_Pad)_22") (pintype "power_in"))
      (node (ref "U5") (pin "23") (pinfunction "GND(Thermal_Pad)_23") (pintype "power_in"))
      (node (ref "U5") (pin "3") (pinfunction "GND_3") (pintype "power_in"))
      (node (ref "U5") (pin "8") (pinfunction "GND_8") (pintype "power_in"))
      (node (ref "U5") (pin "9") (pinfunction "GND_9") (pintype "power_in"))
    )
    (net (code "10") (name "Net-(CR1-Pad1)") (class "Default")
      (node (ref "CR1") (pin "1") (pinfunction "1_1") (pintype "passive"))
      (node (ref "J38") (pin "3") (pinfunction "3_3") (pintype "passive"))
      (node (ref "J38") (pin "4") (pinfunction "4_4") (pintype "passive"))
    )
    (net (code "11") (name "Net-(CR1-Pad2)") (class "Default")
      (node (ref "CR1") (pin "2") (pinfunction "2_2") (pintype "passive"))
      (node (ref "F1") (pin "1") (pinfunction "1_1") (pintype "passive"))
    )
    (net (code "12") (name "Net-(D4-C)") (class "Default")
      (node (ref "D4") (pin "1") (pinfunction "C_1") (pintype "passive"))
      (node (ref "R1") (pin "2") (pinfunction "2_2") (pintype "passive"))
    )
    (net (code "13") (name "Net-(D20-C)") (class "Default")
      (node (ref "D20") (pin "1") (pinfunction "C_1") (pintype "passive"))
      (node (ref "R77") (pin "2") (pinfunction "2_2") (pintype "passive"))
    )
    (net (code "14") (name "Net-(R2-Pad2)") (class "Default")
      (node (ref "R2") (pin "2") (pinfunction "2_2") (pintype "passive"))
      (node (ref "R3") (pin "1") (pinfunction "1_1") (pintype "passive"))
    )
    (net (code "15") (name "Net-(R26-Pad1)") (class "Default")
      (node (ref "R26") (pin "1") (pinfunction "1_1") (pintype "passive"))
      (node (ref "R27") (pin "2") (pinfunction "2_2") (pintype "passive"))
    )
    (net (code "16") (name "Net-(R61-Pad1)") (class "Default")
      (node (ref "R61") (pin "1") (pinfunction "1_1") (pintype "passive"))
      (node (ref "R63") (pin "2") (pinfunction "2_2") (pintype "passive"))
    )
    (net (code "17") (name "Net-(R67-Pad2)") (class "Default")
      (node (ref "R67") (pin "2") (pinfunction "2_2") (pintype "passive"))
      (node (ref "R68") (pin "1") (pinfunction "1_1") (pintype "passive"))
    )
    (net (code "18") (name "Net-(U1-EN)") (class "Default")
      (node (ref "R4") (pin "2") (pinfunction "2_2") (pintype "passive"))
      (node (ref "U1") (pin "8") (pinfunction "EN_8") (pintype "input"))
    )
    (net (code "19") (name "Net-(U1-FB)") (class "Default")
      (node (ref "R2") (pin "1") (pinfunction "1_1") (pintype "passive"))
      (node (ref "U1") (pin "16") (pinfunction "FB_16") (pintype "input"))
    )
    (net (code "20") (name "Net-(U1-PGOOD)") (class "Default")
      (node (ref "R5") (pin "1") (pinfunction "1_1") (pintype "passive"))
      (node (ref "U1") (pin "9") (pinfunction "PGOOD_9") (pintype "output"))
    )
    (net (code "21") (name "Net-(U2-A0)") (class "Default")
      (node (ref "R62") (pin "1") (pinfunction "1_1") (pintype "passive"))
      (node (ref "U2") (pin "2") (pinfunction "A0_2") (pintype "input"))
    )
    (net (code "22") (name "Net-(U2-A1)") (class "Default")
      (node (ref "R64") (pin "1") (pinfunction "1_1") (pintype "passive"))
      (node (ref "U2") (pin "1") (pinfunction "A1_1") (pintype "input"))
    )
    (net (code "23") (name "Net-(U5-ON{slash}OFF)") (class "Default")
      (node (ref "R6") (pin "2") (pinfunction "2_2") (pintype "passive"))
      (node (ref "R60") (pin "2") (pinfunction "2_2") (pintype "passive"))
      (node (ref "U5") (pin "12") (pinfunction "ON/OFF_12") (pintype "input"))
    )
    (net (code "24") (name "Net-(U5-PWGOOD)") (class "Default")
      (node (ref "R59") (pin "2") (pinfunction "2_2") (pintype "passive"))
      (node (ref "R9") (pin "2") (pinfunction "2_2") (pintype "passive"))
      (node (ref "U5") (pin "11") (pinfunction "PWGOOD_11") (pintype "open_collector"))
    )
    (net (code "25") (name "Net-(U5-Trim)") (class "Default")
      (node (ref "R26") (pin "2") (pinfunction "2_2") (pintype "passive"))
      (node (ref "U5") (pin "4") (pinfunction "Trim_4") (pintype "passive"))
    )
    (net (code "26") (name "Net-(U17-A0)") (class "Default")
      (node (ref "R65") (pin "1") (pinfunction "1_1") (pintype "passive"))
      (node (ref "U17") (pin "2") (pinfunction "A0_2") (pintype "input"))
    )
    (net (code "27") (name "Net-(U17-A1)") (class "Default")
      (node (ref "R66") (pin "1") (pinfunction "1_1") (pintype "passive"))
      (node (ref "U17") (pin "1") (pinfunction "A1_1") (pintype "input"))
    )
    (net (code "28") (name "Net-(U18-ON{slash}OFF)") (class "Default")
      (node (ref "R129") (pin "2") (pinfunction "2_2") (pintype "passive"))
      (node (ref "R185") (pin "2") (pinfunction "2_2") (pintype "passive"))
      (node (ref "U18") (pin "12") (pinfunction "ON/OFF_12") (pintype "input"))
    )
    (net (code "29") (name "Net-(U18-PWGOOD)") (class "Default")
      (node (ref "R183") (pin "2") (pinfunction "2_2") (pintype "passive"))
      (node (ref "R184") (pin "2") (pinfunction "2_2") (pintype "passive"))
      (node (ref "U18") (pin "11") (pinfunction "PWGOOD_11") (pintype "open_collector"))
    )
    (net (code "30") (name "Net-(U18-Trim)") (class "Default")
      (node (ref "R61") (pin "2") (pinfunction "2_2") (pintype "passive"))
      (node (ref "U18") (pin "4") (pinfunction "Trim_4") (pintype "passive"))
    )
    (net (code "31") (name "Net-(U19-A0)") (class "Default")
      (node (ref "R79") (pin "1") (pinfunction "1_1") (pintype "passive"))
      (node (ref "U19") (pin "2") (pinfunction "A0_2") (pintype "input"))
    )
    (net (code "32") (name "Net-(U19-A1)") (class "Default")
      (node (ref "R80") (pin "1") (pinfunction "1_1") (pintype "passive"))
      (node (ref "U19") (pin "1") (pinfunction "A1_1") (pintype "input"))
    )
    (net (code "33") (name "Net-(U24-EN)") (class "Default")
      (node (ref "R69") (pin "2") (pinfunction "2_2") (pintype "passive"))
      (node (ref "U24") (pin "8") (pinfunction "EN_8") (pintype "input"))
    )
    (net (code "34") (name "Net-(U24-PGOOD)") (class "Default")
      (node (ref "R70") (pin "1") (pinfunction "1_1") (pintype "passive"))
      (node (ref "U24") (pin "9") (pinfunction "PGOOD_9") (pintype "output"))
    )
    (net (code "35") (name "P3V3_MUN_FB") (class "Default")
      (node (ref "R67") (pin "1") (pinfunction "1_1") (pintype "passive"))
      (node (ref "U24") (pin "16") (pinfunction "FB_16") (pintype "input"))
    )
    (net (code "36") (name "P3V3_MUN_PHASE") (class "Default")
      (node (ref "U24") (pin "2") (pinfunction "PHASE_2") (pintype "output"))
      (node (ref "U24") (pin "22") (pinfunction "PHASE_TPD_22") (pintype "output"))
      (node (ref "U24") (pin "3") (pinfunction "PHASE_3") (pintype "output"))
      (node (ref "U24") (pin "4") (pinfunction "PHASE_4") (pintype "output"))
    )
    (net (code "37") (name "P3V3_MUN_VCC") (class "Default")
      (node (ref "C5") (pin "1") (pinfunction "1_1") (pintype "passive"))
      (node (ref "U24") (pin "17") (pinfunction "VCC_17") (pintype "power_in"))
    )
    (net (code "38") (name "P3V3_SENSE") (class "Default")
      (node (ref "R68") (pin "2") (pinfunction "2_2") (pintype "passive"))
      (node (ref "R72") (pin "1") (pinfunction "1_1") (pintype "passive"))
      (node (ref "U18") (pin "5") (pinfunction "Sense_5") (pintype "passive"))
      (node (ref "U18") (pin "6") (pinfunction "Vout_6") (pintype "power_in"))
      (node (ref "U18") (pin "7") (pinfunction "Vout_7") (pintype "power_in"))
      (node (ref "U19") (pin "8") (pinfunction "VIN+_8") (pintype "input"))
      (node (ref "U24") (pin "10") (pinfunction "VOUT_10") (pintype "output"))
      (node (ref "U24") (pin "11") (pinfunction "VOUT_11") (pintype "output"))
      (node (ref "U24") (pin "12") (pinfunction "VOUT_12") (pintype "output"))
      (node (ref "U24") (pin "13") (pinfunction "VOUT_13") (pintype "output"))
      (node (ref "U24") (pin "14") (pinfunction "VOUT_14") (pintype "output"))
      (node (ref "U24") (pin "24") (pinfunction "VOUT_TPD_24") (pintype "output"))
    )
    (net (code "39") (name "P5V_MUN_VCC") (class "Default")
      (node (ref "C3") (pin "1") (pinfunction "1_1") (pintype "passive"))
      (node (ref "U1") (pin "17") (pinfunction "VCC_17") (pintype "power_in"))
    )
    (net (code "40") (name "P5V_SENSE") (class "Default")
      (node (ref "R3") (pin "2") (pinfunction "2_2") (pintype "passive"))
      (node (ref "R8") (pin "1") (pinfunction "1_1") (pintype "passive"))
      (node (ref "U1") (pin "10") (pinfunction "VOUT_10") (pintype "output"))
      (node (ref "U1") (pin "11") (pinfunction "VOUT_11") (pintype "output"))
      (node (ref "U1") (pin "12") (pinfunction "VOUT_12") (pintype "output"))
      (node (ref "U1") (pin "13") (pinfunction "VOUT_13") (pintype "output"))
      (node (ref "U1") (pin "14") (pinfunction "VOUT_14") (pintype "output"))
      (node (ref "U1") (pin "24") (pinfunction "VOUT_TPD_24") (pintype "output"))
      (node (ref "U17") (pin "8") (pinfunction "VIN+_8") (pintype "input"))
      (node (ref "U5") (pin "5") (pinfunction "Sense_5") (pintype "passive"))
      (node (ref "U5") (pin "6") (pinfunction "Vout_6") (pintype "power_in"))
      (node (ref "U5") (pin "7") (pinfunction "Vout_7") (pintype "power_in"))
    )
    (net (code "41") (name "SENS1_I2C_SCL") (class "Default")
      (node (ref "R188") (pin "1") (pinfunction "1_1") (pintype "passive"))
      (node (ref "U17") (pin "4") (pinfunction "SCL_4") (pintype "bidirectional"))
    )
    (net (code "42") (name "SENS1_I2C_SDA") (class "Default")
      (node (ref "R187") (pin "1") (pinfunction "1_1") (pintype "passive"))
      (node (ref "U17") (pin "3") (pinfunction "SDA_3") (pintype "bidirectional"))
    )
    (net (code "43") (name "SENS_I2C_SCL") (class "Default")
      (node (ref "U19") (pin "4") (pinfunction "SCL_4") (pintype "bidirectional"))
      (node (ref "U2") (pin "4") (pinfunction "SCL_4") (pintype "bidirectional"))
    )
    (net (code "44") (name "SENS_I2C_SDA") (class "Default")
      (node (ref "U19") (pin "3") (pinfunction "SDA_3") (pintype "bidirectional"))
      (node (ref "U2") (pin "3") (pinfunction "SDA_3") (pintype "bidirectional"))
    )
    (net (code "45") (name "unconnected-(U1-BST-Pad18)") (class "Default")
      (node (ref "U1") (pin "18") (pinfunction "BST_18") (pintype "power_in"))
    )
    (net (code "46") (name "unconnected-(U24-BST-Pad18)") (class "Default")
      (node (ref "U24") (pin "18") (pinfunction "BST_18") (pintype "power_in"))
    )
  )
)
